# TM4C123GH6PM.net
KiCad netlist of a schematic drawn in EAGLE
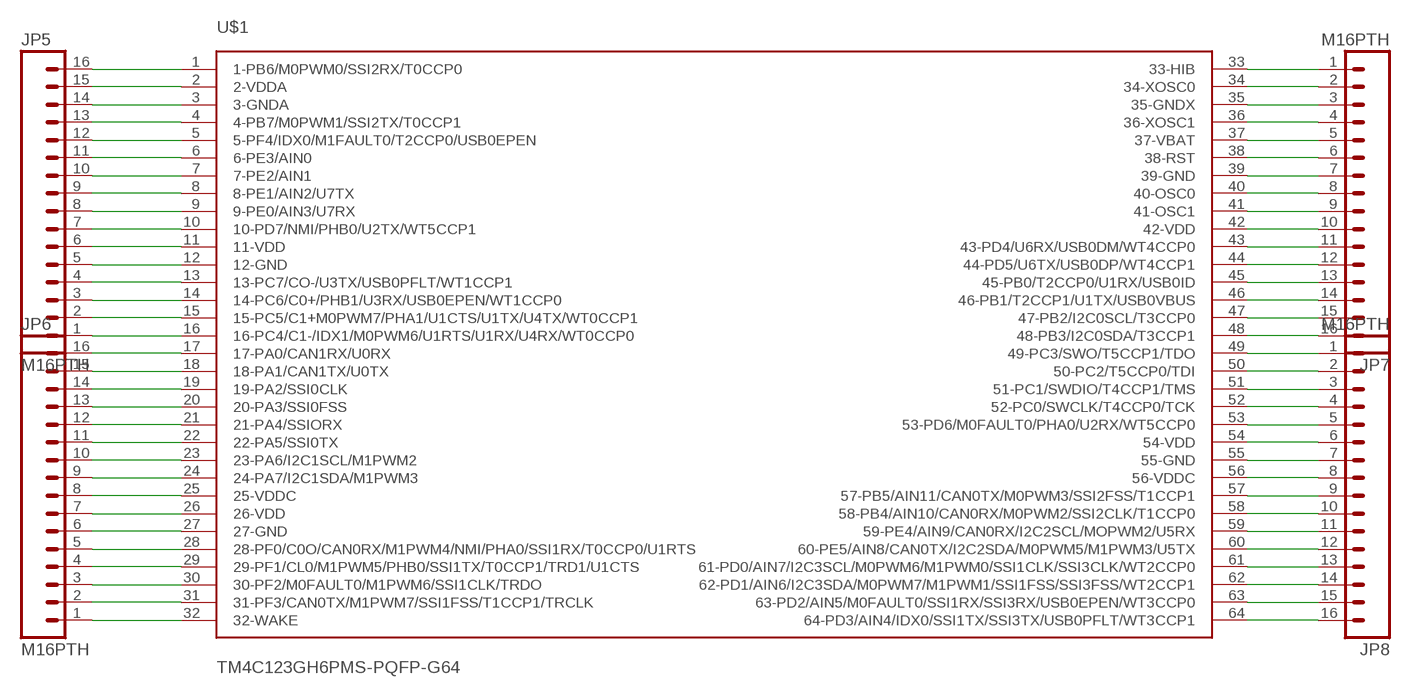
[diagram p0: schematic, sheet 1]

(export (version "E")
  (design (tool "Eeschema 10.0.6"))
  (components
    (comp (ref "JP5")
      (value "M16PTH")
      (footprint "eagle-import:1X16")
      (libsource (lib "eagle-import") (part "M16PTH"))
    )
    (comp (ref "JP6")
      (value "M16PTH")
      (footprint "eagle-import:1X16")
      (libsource (lib "eagle-import") (part "M16PTH"))
    )
    (comp (ref "JP7")
      (value "M16PTH")
      (footprint "eagle-import:1X16")
      (libsource (lib "eagle-import") (part "M16PTH"))
    )
    (comp (ref "JP8")
      (value "M16PTH")
      (footprint "eagle-import:1X16")
      (libsource (lib "eagle-import") (part "M16PTH"))
    )
    (comp (ref "U$1")
      (value "TM4C123GH6PMS-PQFP-G64")
      (footprint "eagle-import:LQFP")
      (libsource (lib "eagle-import") (part "TM4C123GH6PMS-PQFP-G64"))
    )
  )
  (nets
    (net (code "1") (name "Net-(U$1-1-PB6{slash}M0PWM0{slash}SSI2RX{slash}T0CCP0)") (class "Default")
      (node (ref "JP5") (pin "16") (pinfunction "16_16") (pintype "passive"))
      (node (ref "U$1") (pin "1") (pinfunction "1-PB6/M0PWM0/SSI2RX/T0CCP0_1") (pintype "bidirectional"))
    )
    (net (code "2") (name "Net-(U$1-2-VDDA)") (class "Default")
      (node (ref "JP5") (pin "15") (pinfunction "15_15") (pintype "passive"))
      (node (ref "U$1") (pin "2") (pinfunction "2-VDDA_2") (pintype "bidirectional"))
    )
    (net (code "3") (name "Net-(U$1-3-GNDA)") (class "Default")
      (node (ref "JP5") (pin "14") (pinfunction "14_14") (pintype "passive"))
      (node (ref "U$1") (pin "3") (pinfunction "3-GNDA_3") (pintype "bidirectional"))
    )
    (net (code "4") (name "Net-(U$1-4-PB7{slash}M0PWM1{slash}SSI2TX{slash}T0CCP1)") (class "Default")
      (node (ref "JP5") (pin "13") (pinfunction "13_13") (pintype "passive"))
      (node (ref "U$1") (pin "4") (pinfunction "4-PB7/M0PWM1/SSI2TX/T0CCP1_4") (pintype "bidirectional"))
    )
    (net (code "5") (name "Net-(U$1-5-PF4{slash}IDX0{slash}M1FAULT0{slash}T2CCP0{slash}USB0EPEN)") (class "Default")
      (node (ref "JP5") (pin "12") (pinfunction "12_12") (pintype "passive"))
      (node (ref "U$1") (pin "5") (pinfunction "5-PF4/IDX0/M1FAULT0/T2CCP0/USB0EPEN_5") (pintype "bidirectional"))
    )
    (net (code "6") (name "Net-(U$1-6-PE3{slash}AIN0)") (class "Default")
      (node (ref "JP5") (pin "11") (pinfunction "11_11") (pintype "passive"))
      (node (ref "U$1") (pin "6") (pinfunction "6-PE3/AIN0_6") (pintype "bidirectional"))
    )
    (net (code "7") (name "Net-(U$1-7-PE2{slash}AIN1)") (class "Default")
      (node (ref "JP5") (pin "10") (pinfunction "10_10") (pintype "passive"))
      (node (ref "U$1") (pin "7") (pinfunction "7-PE2/AIN1_7") (pintype "bidirectional"))
    )
    (net (code "8") (name "Net-(U$1-8-PE1{slash}AIN2{slash}U7TX)") (class "Default")
      (node (ref "JP5") (pin "9") (pinfunction "9_9") (pintype "passive"))
      (node (ref "U$1") (pin "8") (pinfunction "8-PE1/AIN2/U7TX_8") (pintype "bidirectional"))
    )
    (net (code "9") (name "Net-(U$1-9-PE0{slash}AIN3{slash}U7RX)") (class "Default")
      (node (ref "JP5") (pin "8") (pinfunction "8_8") (pintype "passive"))
      (node (ref "U$1") (pin "9") (pinfunction "9-PE0/AIN3/U7RX_9") (pintype "bidirectional"))
    )
    (net (code "10") (name "Net-(U$1-10-PD7{slash}NMI{slash}PHB0{slash}U2TX{slash}WT5CCP1)") (class "Default")
      (node (ref "JP5") (pin "7") (pinfunction "7_7") (pintype "passive"))
      (node (ref "U$1") (pin "10") (pinfunction "10-PD7/NMI/PHB0/U2TX/WT5CCP1_10") (pintype "bidirectional"))
    )
    (net (code "11") (name "Net-(U$1-11-VDD)") (class "Default")
      (node (ref "JP5") (pin "6") (pinfunction "6_6") (pintype "passive"))
      (node (ref "U$1") (pin "11") (pinfunction "11-VDD_11") (pintype "bidirectional"))
    )
    (net (code "12") (name "Net-(U$1-12-GND)") (class "Default")
      (node (ref "JP5") (pin "5") (pinfunction "5_5") (pintype "passive"))
      (node (ref "U$1") (pin "12") (pinfunction "12-GND_12") (pintype "bidirectional"))
    )
    (net (code "13") (name "Net-(U$1-13-PC7{slash}CO-{slash}U3TX{slash}USB0PFLT{slash}WT1CCP1)") (class "Default")
      (node (ref "JP5") (pin "4") (pinfunction "4_4") (pintype "passive"))
      (node (ref "U$1") (pin "13") (pinfunction "13-PC7/CO-/U3TX/USB0PFLT/WT1CCP1_13") (pintype "bidirectional"))
    )
    (net (code "14") (name "Net-(U$1-14-PC6{slash}C0+{slash}PHB1{slash}U3RX{slash}USB0EPEN{slash}WT1CCP0)") (class "Default")
      (node (ref "JP5") (pin "3") (pinfunction "3_3") (pintype "passive"))
      (node (ref "U$1") (pin "14") (pinfunction "14-PC6/C0+/PHB1/U3RX/USB0EPEN/WT1CCP0_14") (pintype "bidirectional"))
    )
    (net (code "15") (name "Net-(U$1-15-PC5{slash}C1+M0PWM7{slash}PHA1{slash}U1CTS{slash}U1TX{slash}U4TX{slash}WT0CCP1)") (class "Default")
      (node (ref "JP5") (pin "2") (pinfunction "2_2") (pintype "passive"))
      (node (ref "U$1") (pin "15") (pinfunction "15-PC5/C1+M0PWM7/PHA1/U1CTS/U1TX/U4TX/WT0CCP1_15") (pintype "bidirectional"))
    )
    (net (code "16") (name "Net-(U$1-16-PC4{slash}C1-{slash}IDX1{slash}M0PWM6{slash}U1RTS{slash}U1RX{slash}U4RX{slash}WT0CCP0)") (class "Default")
      (node (ref "JP5") (pin "1") (pinfunction "1_1") (pintype "passive"))
      (node (ref "U$1") (pin "16") (pinfunction "16-PC4/C1-/IDX1/M0PWM6/U1RTS/U1RX/U4RX/WT0CCP0_16") (pintype "bidirectional"))
    )
    (net (code "17") (name "Net-(U$1-17-PA0{slash}CAN1RX{slash}U0RX)") (class "Default")
      (node (ref "JP6") (pin "16") (pinfunction "16_16") (pintype "passive"))
      (node (ref "U$1") (pin "17") (pinfunction "17-PA0/CAN1RX/U0RX_17") (pintype "bidirectional"))
    )
    (net (code "18") (name "Net-(U$1-18-PA1{slash}CAN1TX{slash}U0TX)") (class "Default")
      (node (ref "JP6") (pin "15") (pinfunction "15_15") (pintype "passive"))
      (node (ref "U$1") (pin "18") (pinfunction "18-PA1/CAN1TX/U0TX_18") (pintype "bidirectional"))
    )
    (net (code "19") (name "Net-(U$1-19-PA2{slash}SSI0CLK)") (class "Default")
      (node (ref "JP6") (pin "14") (pinfunction "14_14") (pintype "passive"))
      (node (ref "U$1") (pin "19") (pinfunction "19-PA2/SSI0CLK_19") (pintype "bidirectional"))
    )
    (net (code "20") (name "Net-(U$1-20-PA3{slash}SSI0FSS)") (class "Default")
      (node (ref "JP6") (pin "13") (pinfunction "13_13") (pintype "passive"))
      (node (ref "U$1") (pin "20") (pinfunction "20-PA3/SSI0FSS_20") (pintype "bidirectional"))
    )
    (net (code "21") (name "Net-(U$1-21-PA4{slash}SSIORX)") (class "Default")
      (node (ref "JP6") (pin "12") (pinfunction "12_12") (pintype "passive"))
      (node (ref "U$1") (pin "21") (pinfunction "21-PA4/SSIORX_21") (pintype "bidirectional"))
    )
    (net (code "22") (name "Net-(U$1-22-PA5{slash}SSI0TX)") (class "Default")
      (node (ref "JP6") (pin "11") (pinfunction "11_11") (pintype "passive"))
      (node (ref "U$1") (pin "22") (pinfunction "22-PA5/SSI0TX_22") (pintype "bidirectional"))
    )
    (net (code "23") (name "Net-(U$1-23-PA6{slash}I2C1SCL{slash}M1PWM2)") (class "Default")
      (node (ref "JP6") (pin "10") (pinfunction "10_10") (pintype "passive"))
      (node (ref "U$1") (pin "23") (pinfunction "23-PA6/I2C1SCL/M1PWM2_23") (pintype "bidirectional"))
    )
    (net (code "24") (name "Net-(U$1-24-PA7{slash}I2C1SDA{slash}M1PWM3)") (class "Default")
      (node (ref "JP6") (pin "9") (pinfunction "9_9") (pintype "passive"))
      (node (ref "U$1") (pin "24") (pinfunction "24-PA7/I2C1SDA/M1PWM3_24") (pintype "bidirectional"))
    )
    (net (code "25") (name "Net-(U$1-25-VDDC)") (class "Default")
      (node (ref "JP6") (pin "8") (pinfunction "8_8") (pintype "passive"))
      (node (ref "U$1") (pin "25") (pinfunction "25-VDDC_25") (pintype "bidirectional"))
    )
    (net (code "26") (name "Net-(U$1-26-VDD)") (class "Default")
      (node (ref "JP6") (pin "7") (pinfunction "7_7") (pintype "passive"))
      (node (ref "U$1") (pin "26") (pinfunction "26-VDD_26") (pintype "bidirectional"))
    )
    (net (code "27") (name "Net-(U$1-27-GND)") (class "Default")
      (node (ref "JP6") (pin "6") (pinfunction "6_6") (pintype "passive"))
      (node (ref "U$1") (pin "27") (pinfunction "27-GND_27") (pintype "bidirectional"))
    )
    (net (code "28") (name "Net-(U$1-28-PF0{slash}C0O{slash}CAN0RX{slash}M1PWM4{slash}NMI{slash}PHA0{slash}SSI1RX{slash}T0CCP0{slash}U1RTS)") (class "Default")
      (node (ref "JP6") (pin "5") (pinfunction "5_5") (pintype "passive"))
      (node (ref "U$1") (pin "28") (pinfunction "28-PF0/C0O/CAN0RX/M1PWM4/NMI/PHA0/SSI1RX/T0CCP0/U1RTS_28") (pintype "bidirectional"))
    )
    (net (code "29") (name "Net-(U$1-29-PF1{slash}CL0{slash}M1PWM5{slash}PHB0{slash}SSI1TX{slash}T0CCP1{slash}TRD1{slash}U1CTS)") (class "Default")
      (node (ref "JP6") (pin "4") (pinfunction "4_4") (pintype "passive"))
      (node (ref "U$1") (pin "29") (pinfunction "29-PF1/CL0/M1PWM5/PHB0/SSI1TX/T0CCP1/TRD1/U1CTS_29") (pintype "bidirectional"))
    )
    (net (code "30") (name "Net-(U$1-30-PF2{slash}M0FAULT0{slash}M1PWM6{slash}SSI1CLK{slash}TRDO)") (class "Default")
      (node (ref "JP6") (pin "3") (pinfunction "3_3") (pintype "passive"))
      (node (ref "U$1") (pin "30") (pinfunction "30-PF2/M0FAULT0/M1PWM6/SSI1CLK/TRDO_30") (pintype "bidirectional"))
    )
    (net (code "31") (name "Net-(U$1-31-PF3{slash}CAN0TX{slash}M1PWM7{slash}SSI1FSS{slash}T1CCP1{slash}TRCLK)") (class "Default")
      (node (ref "JP6") (pin "2") (pinfunction "2_2") (pintype "passive"))
      (node (ref "U$1") (pin "31") (pinfunction "31-PF3/CAN0TX/M1PWM7/SSI1FSS/T1CCP1/TRCLK_31") (pintype "bidirectional"))
    )
    (net (code "32") (name "Net-(U$1-32-WAKE)") (class "Default")
      (node (ref "JP6") (pin "1") (pinfunction "1_1") (pintype "passive"))
      (node (ref "U$1") (pin "32") (pinfunction "32-WAKE_32") (pintype "bidirectional"))
    )
    (net (code "33") (name "Net-(U$1-33-HIB)") (class "Default")
      (node (ref "JP7") (pin "1") (pinfunction "1_1") (pintype "passive"))
      (node (ref "U$1") (pin "33") (pinfunction "33-HIB_33") (pintype "bidirectional"))
    )
    (net (code "34") (name "Net-(U$1-34-XOSC0)") (class "Default")
      (node (ref "JP7") (pin "2") (pinfunction "2_2") (pintype "passive"))
      (node (ref "U$1") (pin "34") (pinfunction "34-XOSC0_34") (pintype "bidirectional"))
    )
    (net (code "35") (name "Net-(U$1-35-GNDX)") (class "Default")
      (node (ref "JP7") (pin "3") (pinfunction "3_3") (pintype "passive"))
      (node (ref "U$1") (pin "35") (pinfunction "35-GNDX_35") (pintype "bidirectional"))
    )
    (net (code "36") (name "Net-(U$1-36-XOSC1)") (class "Default")
      (node (ref "JP7") (pin "4") (pinfunction "4_4") (pintype "passive"))
      (node (ref "U$1") (pin "36") (pinfunction "36-XOSC1_36") (pintype "bidirectional"))
    )
    (net (code "37") (name "Net-(U$1-37-VBAT)") (class "Default")
      (node (ref "JP7") (pin "5") (pinfunction "5_5") (pintype "passive"))
      (node (ref "U$1") (pin "37") (pinfunction "37-VBAT_37") (pintype "bidirectional"))
    )
    (net (code "38") (name "Net-(U$1-38-RST)") (class "Default")
      (node (ref "JP7") (pin "6") (pinfunction "6_6") (pintype "passive"))
      (node (ref "U$1") (pin "38") (pinfunction "38-RST_38") (pintype "bidirectional"))
    )
    (net (code "39") (name "Net-(U$1-39-GND)") (class "Default")
      (node (ref "JP7") (pin "7") (pinfunction "7_7") (pintype "passive"))
      (node (ref "U$1") (pin "39") (pinfunction "39-GND_39") (pintype "bidirectional"))
    )
    (net (code "40") (name "Net-(U$1-40-OSC0)") (class "Default")
      (node (ref "JP7") (pin "8") (pinfunction "8_8") (pintype "passive"))
      (node (ref "U$1") (pin "40") (pinfunction "40-OSC0_40") (pintype "bidirectional"))
    )
    (net (code "41") (name "Net-(U$1-41-OSC1)") (class "Default")
      (node (ref "JP7") (pin "9") (pinfunction "9_9") (pintype "passive"))
      (node (ref "U$1") (pin "41") (pinfunction "41-OSC1_41") (pintype "bidirectional"))
    )
    (net (code "42") (name "Net-(U$1-42-VDD)") (class "Default")
      (node (ref "JP7") (pin "10") (pinfunction "10_10") (pintype "passive"))
      (node (ref "U$1") (pin "42") (pinfunction "42-VDD_42") (pintype "bidirectional"))
    )
    (net (code "43") (name "Net-(U$1-43-PD4{slash}U6RX{slash}USB0DM{slash}WT4CCP0)") (class "Default")
      (node (ref "JP7") (pin "11") (pinfunction "11_11") (pintype "passive"))
      (node (ref "U$1") (pin "43") (pinfunction "43-PD4/U6RX/USB0DM/WT4CCP0_43") (pintype "bidirectional"))
    )
    (net (code "44") (name "Net-(U$1-44-PD5{slash}U6TX{slash}USB0DP{slash}WT4CCP1)") (class "Default")
      (node (ref "JP7") (pin "12") (pinfunction "12_12") (pintype "passive"))
      (node (ref "U$1") (pin "44") (pinfunction "44-PD5/U6TX/USB0DP/WT4CCP1_44") (pintype "bidirectional"))
    )
    (net (code "45") (name "Net-(U$1-45-PB0{slash}T2CCP0{slash}U1RX{slash}USB0ID)") (class "Default")
      (node (ref "JP7") (pin "13") (pinfunction "13_13") (pintype "passive"))
      (node (ref "U$1") (pin "45") (pinfunction "45-PB0/T2CCP0/U1RX/USB0ID_45") (pintype "bidirectional"))
    )
    (net (code "46") (name "Net-(U$1-46-PB1{slash}T2CCP1{slash}U1TX{slash}USB0VBUS)") (class "Default")
      (node (ref "JP7") (pin "14") (pinfunction "14_14") (pintype "passive"))
      (node (ref "U$1") (pin "46") (pinfunction "46-PB1/T2CCP1/U1TX/USB0VBUS_46") (pintype "bidirectional"))
    )
    (net (code "47") (name "Net-(U$1-47-PB2{slash}I2C0SCL{slash}T3CCP0)") (class "Default")
      (node (ref "JP7") (pin "15") (pinfunction "15_15") (pintype "passive"))
      (node (ref "U$1") (pin "47") (pinfunction "47-PB2/I2C0SCL/T3CCP0_47") (pintype "bidirectional"))
    )
    (net (code "48") (name "Net-(U$1-48-PB3{slash}I2C0SDA{slash}T3CCP1)") (class "Default")
      (node (ref "JP7") (pin "16") (pinfunction "16_16") (pintype "passive"))
      (node (ref "U$1") (pin "48") (pinfunction "48-PB3/I2C0SDA/T3CCP1_48") (pintype "bidirectional"))
    )
    (net (code "49") (name "Net-(U$1-49-PC3{slash}SWO{slash}T5CCP1{slash}TDO)") (class "Default")
      (node (ref "JP8") (pin "1") (pinfunction "1_1") (pintype "passive"))
      (node (ref "U$1") (pin "49") (pinfunction "49-PC3/SWO/T5CCP1/TDO_49") (pintype "bidirectional"))
    )
    (net (code "50") (name "Net-(U$1-50-PC2{slash}T5CCP0{slash}TDI)") (class "Default")
      (node (ref "JP8") (pin "2") (pinfunction "2_2") (pintype "passive"))
      (node (ref "U$1") (pin "50") (pinfunction "50-PC2/T5CCP0/TDI_50") (pintype "bidirectional"))
    )
    (net (code "51") (name "Net-(U$1-51-PC1{slash}SWDIO{slash}T4CCP1{slash}TMS)") (class "Default")
      (node (ref "JP8") (pin "3") (pinfunction "3_3") (pintype "passive"))
      (node (ref "U$1") (pin "51") (pinfunction "51-PC1/SWDIO/T4CCP1/TMS_51") (pintype "bidirectional"))
    )
    (net (code "52") (name "Net-(U$1-52-PC0{slash}SWCLK{slash}T4CCP0{slash}TCK)") (class "Default")
      (node (ref "JP8") (pin "4") (pinfunction "4_4") (pintype "passive"))
      (node (ref "U$1") (pin "52") (pinfunction "52-PC0/SWCLK/T4CCP0/TCK_52") (pintype "bidirectional"))
    )
    (net (code "53") (name "Net-(U$1-53-PD6{slash}M0FAULT0{slash}PHA0{slash}U2RX{slash}WT5CCP0)") (class "Default")
      (node (ref "JP8") (pin "5") (pinfunction "5_5") (pintype "passive"))
      (node (ref "U$1") (pin "53") (pinfunction "53-PD6/M0FAULT0/PHA0/U2RX/WT5CCP0_53") (pintype "bidirectional"))
    )
    (net (code "54") (name "Net-(U$1-54-VDD)") (class "Default")
      (node (ref "JP8") (pin "6") (pinfunction "6_6") (pintype "passive"))
      (node (ref "U$1") (pin "54") (pinfunction "54-VDD_54") (pintype "bidirectional"))
    )
    (net (code "55") (name "Net-(U$1-55-GND)") (class "Default")
      (node (ref "JP8") (pin "7") (pinfunction "7_7") (pintype "passive"))
      (node (ref "U$1") (pin "55") (pinfunction "55-GND_55") (pintype "bidirectional"))
    )
    (net (code "56") (name "Net-(U$1-56-VDDC)") (class "Default")
      (node (ref "JP8") (pin "8") (pinfunction "8_8") (pintype "passive"))
      (node (ref "U$1") (pin "56") (pinfunction "56-VDDC_56") (pintype "bidirectional"))
    )
    (net (code "57") (name "Net-(U$1-57-PB5{slash}AIN11{slash}CAN0TX{slash}M0PWM3{slash}SSI2FSS{slash}T1CCP1)") (class "Default")
      (node (ref "JP8") (pin "9") (pinfunction "9_9") (pintype "passive"))
      (node (ref "U$1") (pin "57") (pinfunction "57-PB5/AIN11/CAN0TX/M0PWM3/SSI2FSS/T1CCP1_57") (pintype "bidirectional"))
    )
    (net (code "58") (name "Net-(U$1-58-PB4{slash}AIN10{slash}CAN0RX{slash}M0PWM2{slash}SSI2CLK{slash}T1CCP0)") (class "Default")
      (node (ref "JP8") (pin "10") (pinfunction "10_10") (pintype "passive"))
      (node (ref "U$1") (pin "58") (pinfunction "58-PB4/AIN10/CAN0RX/M0PWM2/SSI2CLK/T1CCP0_58") (pintype "bidirectional"))
    )
    (net (code "59") (name "Net-(U$1-59-PE4{slash}AIN9{slash}CAN0RX{slash}I2C2SCL{slash}MOPWM2{slash}U5RX)") (class "Default")
      (node (ref "JP8") (pin "11") (pinfunction "11_11") (pintype "passive"))
      (node (ref "U$1") (pin "59") (pinfunction "59-PE4/AIN9/CAN0RX/I2C2SCL/MOPWM2/U5RX_59") (pintype "bidirectional"))
    )
    (net (code "60") (name "Net-(U$1-60-PE5{slash}AIN8{slash}CAN0TX{slash}I2C2SDA{slash}M0PWM5{slash}M1PWM3{slash}U5TX)") (class "Default")
      (node (ref "JP8") (pin "12") (pinfunction "12_12") (pintype "passive"))
      (node (ref "U$1") (pin "60") (pinfunction "60-PE5/AIN8/CAN0TX/I2C2SDA/M0PWM5/M1PWM3/U5TX_60") (pintype "bidirectional"))
    )
    (net (code "61") (name "Net-(U$1-61-PD0{slash}AIN7{slash}I2C3SCL{slash}M0PWM6{slash}M1PWM0{slash}SSI1CLK{slash}SSI3CLK{slash}WT2CCP0)") (class "Default")
      (node (ref "JP8") (pin "13") (pinfunction "13_13") (pintype "passive"))
      (node (ref "U$1") (pin "61") (pinfunction "61-PD0/AIN7/I2C3SCL/M0PWM6/M1PWM0/SSI1CLK/SSI3CLK/WT2CCP0_61") (pintype "bidirectional"))
    )
    (net (code "62") (name "Net-(U$1-62-PD1{slash}AIN6{slash}I2C3SDA{slash}M0PWM7{slash}M1PWM1{slash}SSI1FSS{slash}SSI3FSS{slash}WT2CCP1)") (class "Default")
      (node (ref "JP8") (pin "14") (pinfunction "14_14") (pintype "passive"))
      (node (ref "U$1") (pin "62") (pinfunction "62-PD1/AIN6/I2C3SDA/M0PWM7/M1PWM1/SSI1FSS/SSI3FSS/WT2CCP1_62") (pintype "bidirectional"))
    )
    (net (code "63") (name "Net-(U$1-63-PD2{slash}AIN5{slash}M0FAULT0{slash}SSI1RX{slash}SSI3RX{slash}USB0EPEN{slash}WT3CCP0)") (class "Default")
      (node (ref "JP8") (pin "15") (pinfunction "15_15") (pintype "passive"))
      (node (ref "U$1") (pin "63") (pinfunction "63-PD2/AIN5/M0FAULT0/SSI1RX/SSI3RX/USB0EPEN/WT3CCP0_63") (pintype "bidirectional"))
    )
    (net (code "64") (name "Net-(U$1-64-PD3{slash}AIN4{slash}IDX0{slash}SSI1TX{slash}SSI3TX{slash}USB0PFLT{slash}WT3CCP1)") (class "Default")
      (node (ref "JP8") (pin "16") (pinfunction "16_16") (pintype "passive"))
      (node (ref "U$1") (pin "64") (pinfunction "64-PD3/AIN4/IDX0/SSI1TX/SSI3TX/USB0PFLT/WT3CCP1_64") (pintype "bidirectional"))
    )
  )
)
